# Pyr0-Piezo-FFC-Direct-Creality-X_MIN_v2_.net
KiCad netlist of a schematic drawn in EAGLE
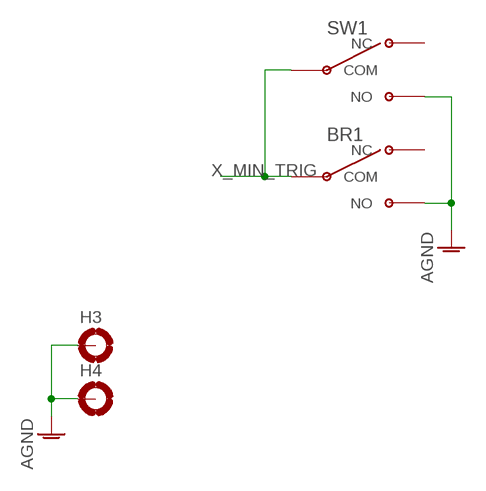
[diagram p0: schematic, sheet 1]

(export (version "E")
  (design (tool "Eeschema 10.0.6"))
  (components
    (comp (ref "BR1")
      (value "LIMIT_SWITCH")
      (footprint "eagle-import:LIMIT_SWITCH_BRIDGE")
      (libsource (lib "eagle-import") (part "LIMIT_SWITCH"))
    )
    (comp (ref "H3")
      (value "HOLES_MOUNT-PAD-ROUND3.2")
      (footprint "eagle-import:HOLES_3,2-PAD")
      (libsource (lib "eagle-import") (part "HOLES_MOUNT-PAD-ROUND3.2"))
    )
    (comp (ref "H4")
      (value "HOLES_MOUNT-PAD-ROUND3.2")
      (footprint "eagle-import:HOLES_3,2-PAD")
      (libsource (lib "eagle-import") (part "HOLES_MOUNT-PAD-ROUND3.2"))
    )
    (comp (ref "SW1")
      (value "LIMIT_SWITCHMICRO_SPDT_5.08")
      (footprint "eagle-import:MICROSWITCH_5.08")
      (libsource (lib "eagle-import") (part "LIMIT_SWITCHMICRO_SPDT_5.08"))
    )
  )
  (nets
    (net (code "1") (name "/X_MIN_TRIG") (class "Default")
      (node (ref "BR1") (pin "COM") (pinfunction "COM_COM") (pintype "bidirectional"))
      (node (ref "SW1") (pin "P$1") (pinfunction "COM_P$1") (pintype "bidirectional"))
    )
    (net (code "2") (name "AGND") (class "Default")
      (node (ref "BR1") (pin "NO") (pinfunction "NO_NO") (pintype "bidirectional"))
      (node (ref "H3") (pin "B3,2") (pinfunction "MOUNT_B3,2") (pintype "passive"))
      (node (ref "H4") (pin "B3,2") (pinfunction "MOUNT_B3,2") (pintype "passive"))
      (node (ref "SW1") (pin "P$2") (pinfunction "NO_P$2") (pintype "bidirectional"))
    )
    (net (code "3") (name "unconnected-(BR1-PadNC)") (class "Default")
      (node (ref "BR1") (pin "NC") (pinfunction "NC_NC") (pintype "bidirectional"))
    )
    (net (code "4") (name "unconnected-(SW1-NC-PadP$3)") (class "Default")
      (node (ref "SW1") (pin "P$3") (pinfunction "NC_P$3") (pintype "bidirectional"))
    )
  )
)
